# ble_blind_mover.net
KiCad netlist of a schematic drawn in EAGLE
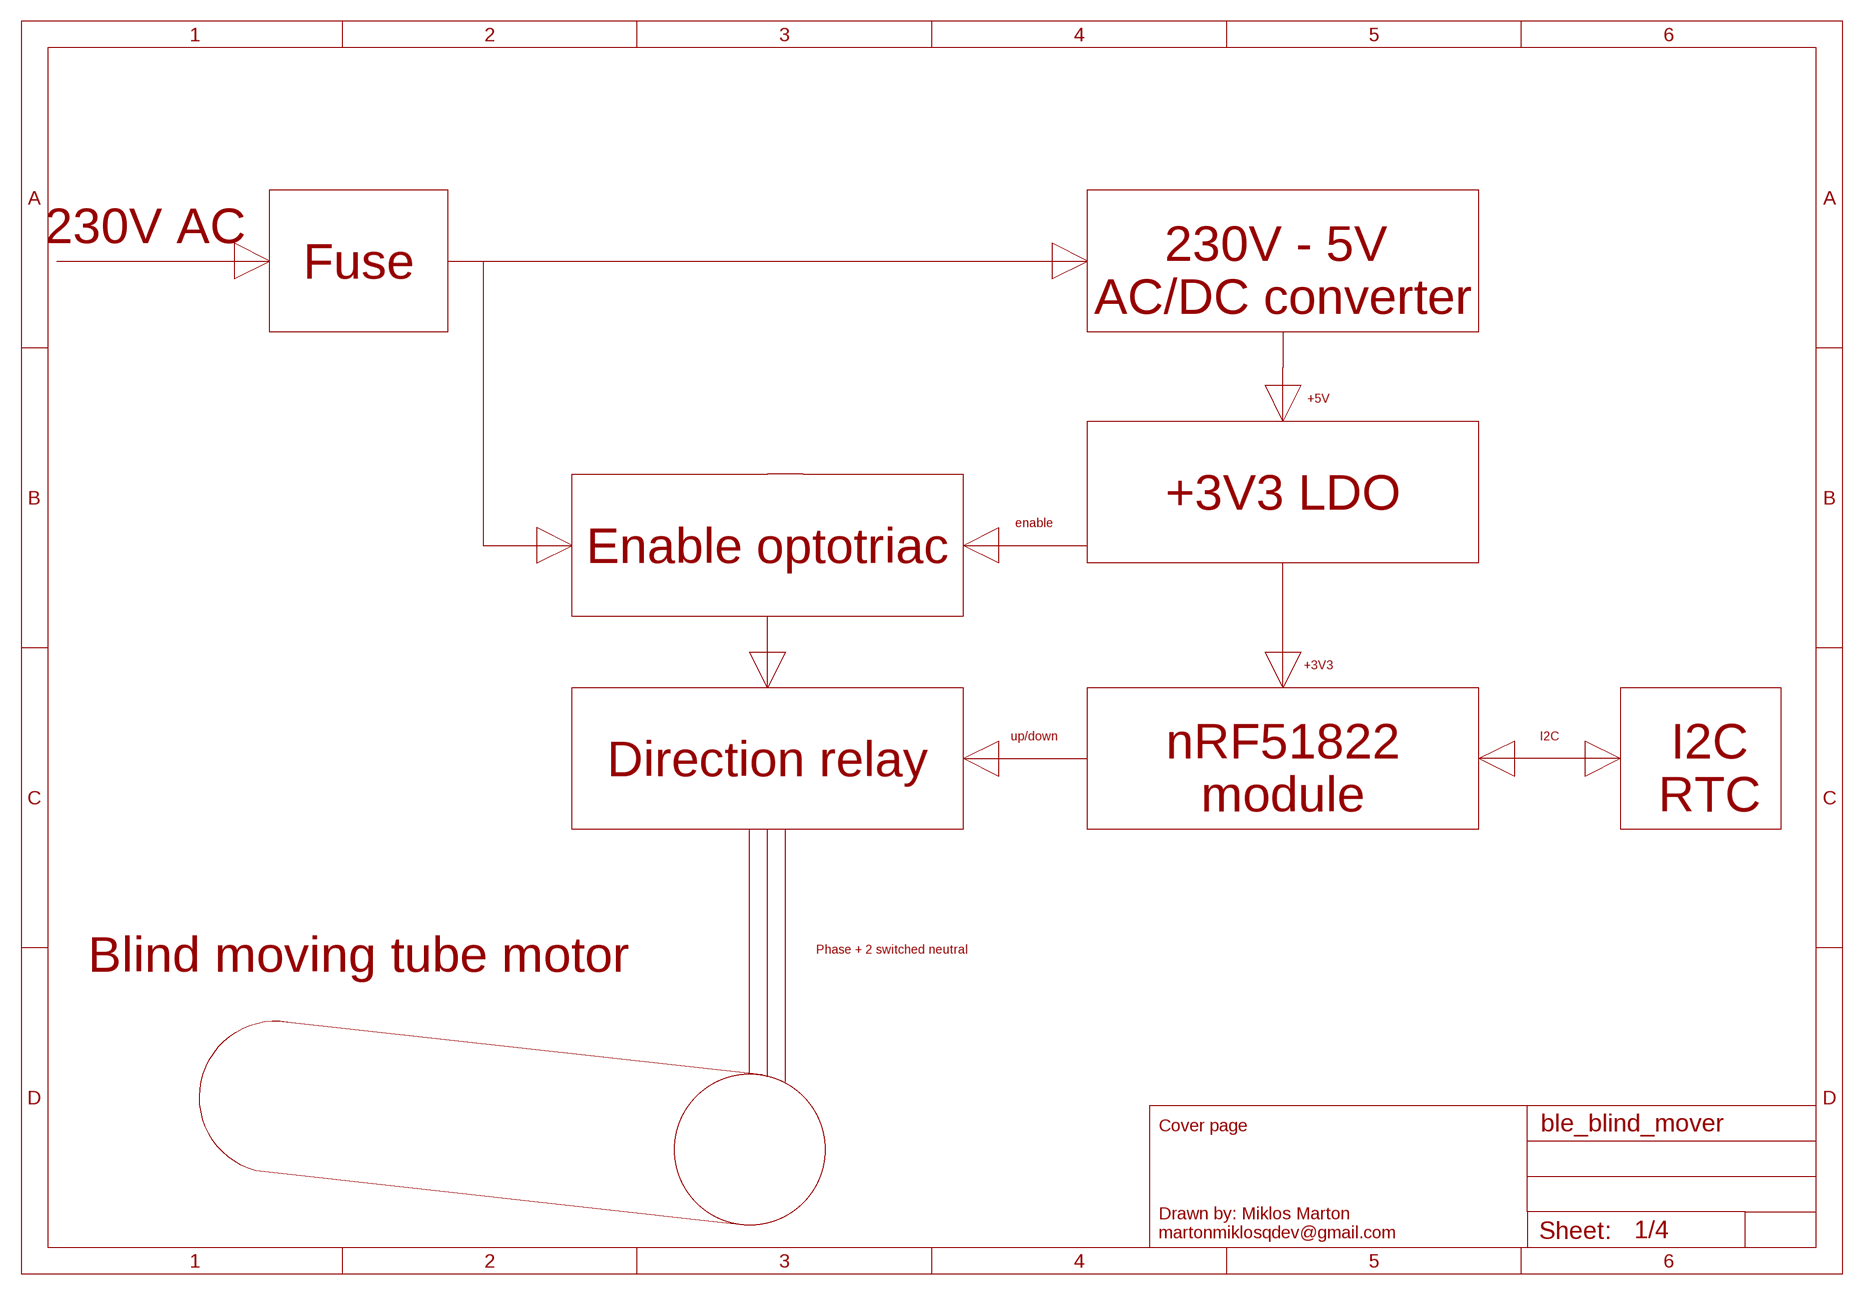
[diagram p0: schematic, sheet 1]
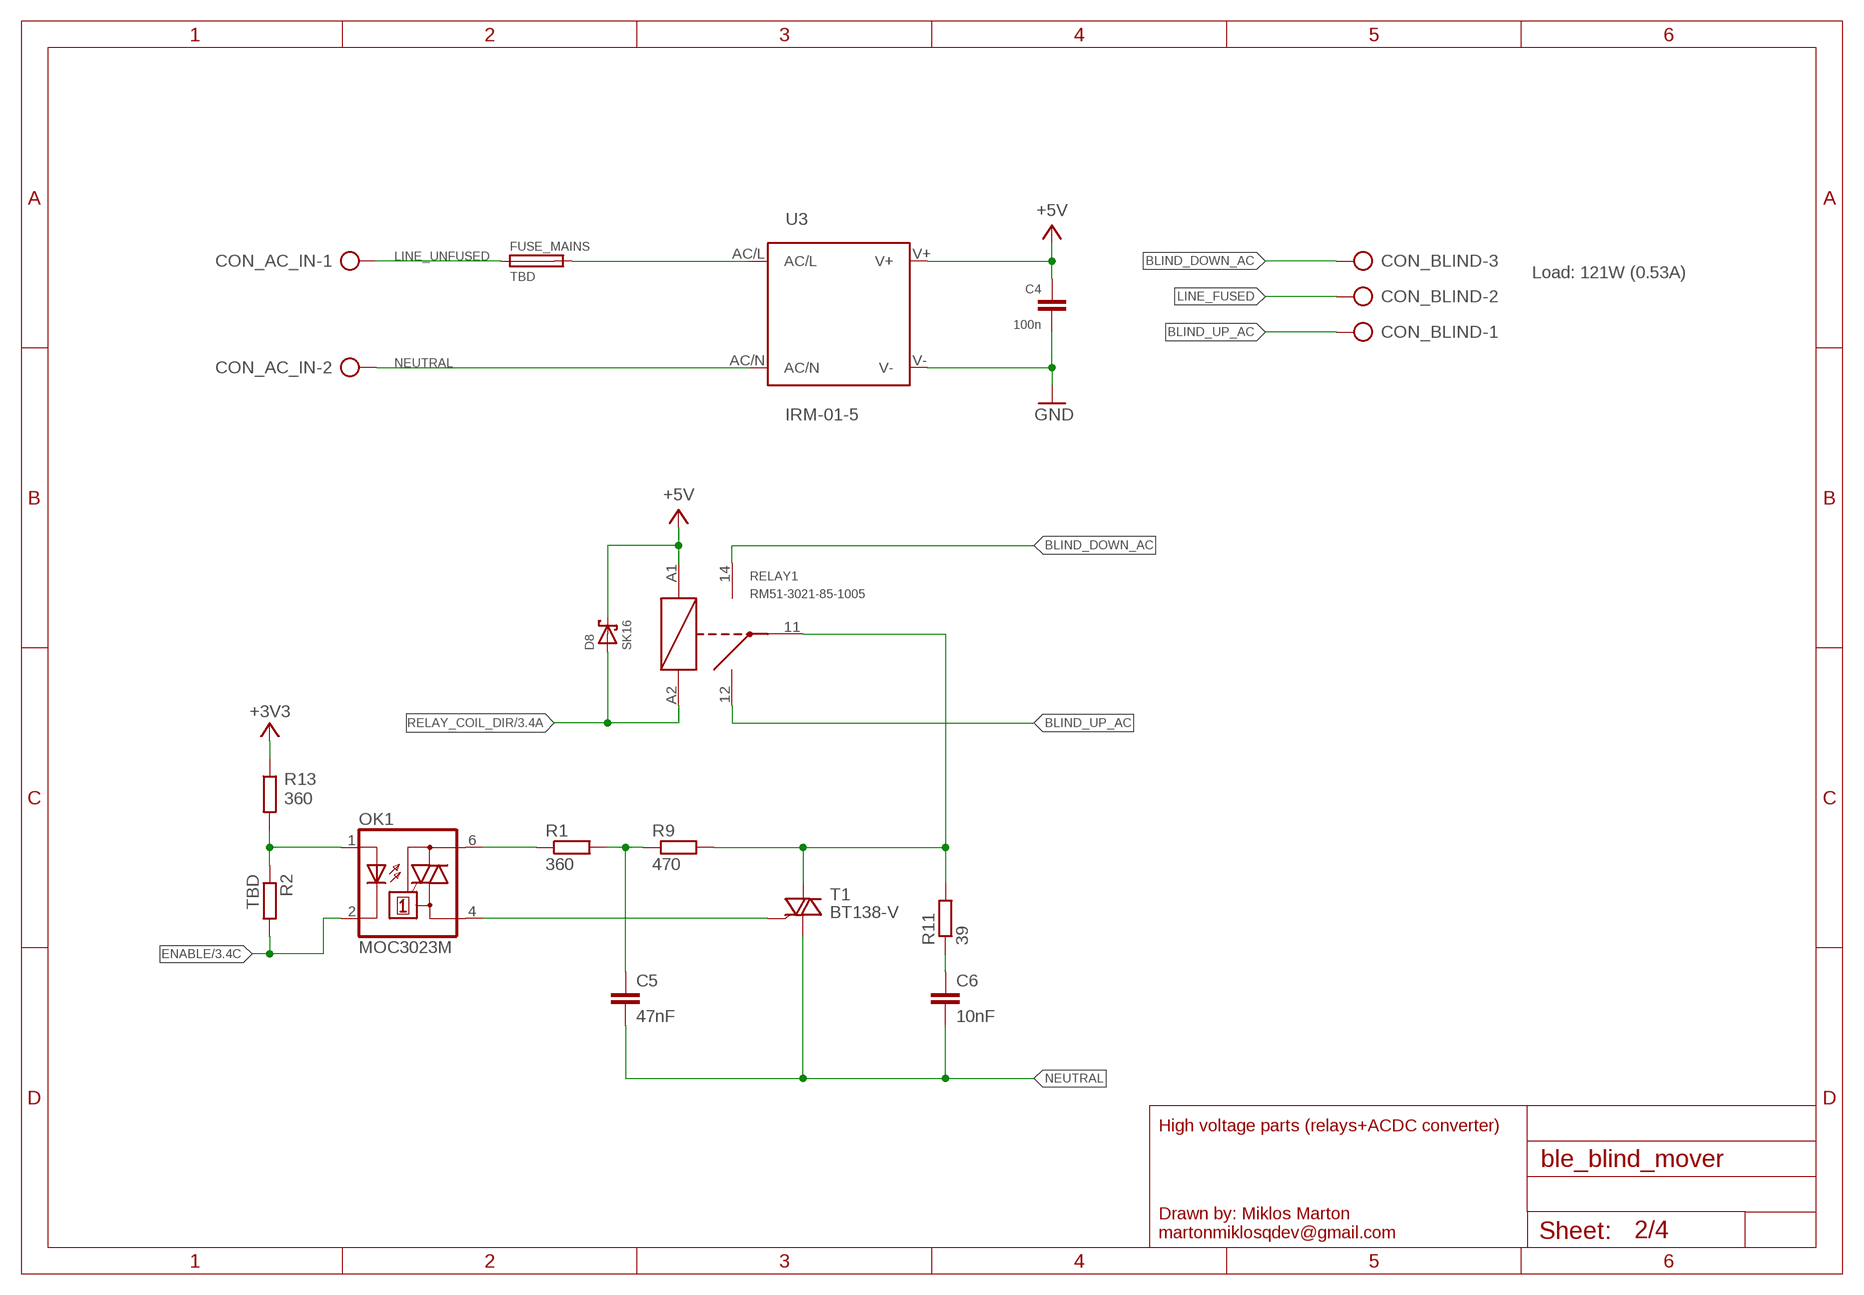
[diagram p1: schematic, sheet 2]
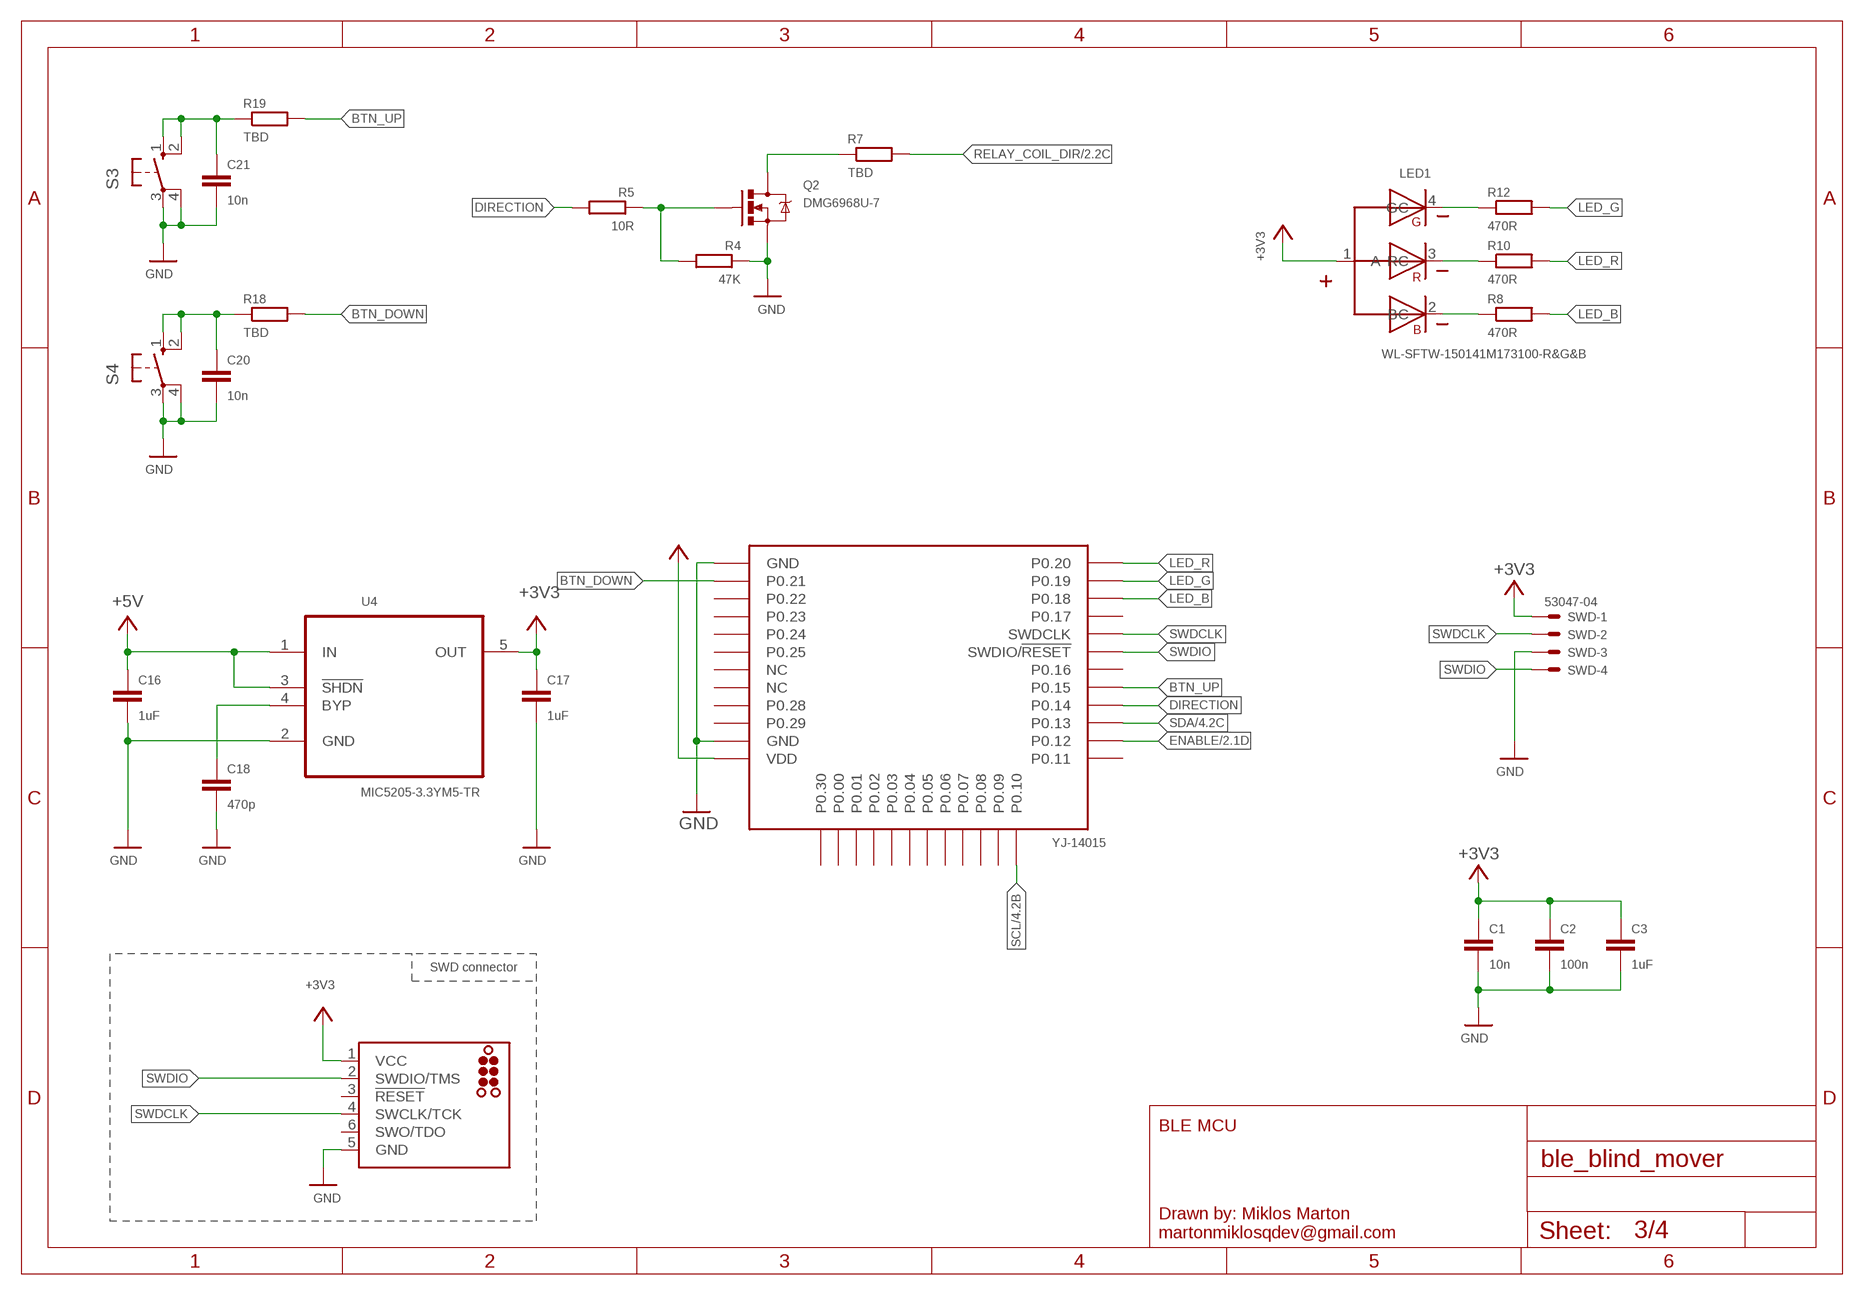
[diagram p2: schematic, sheet 3]
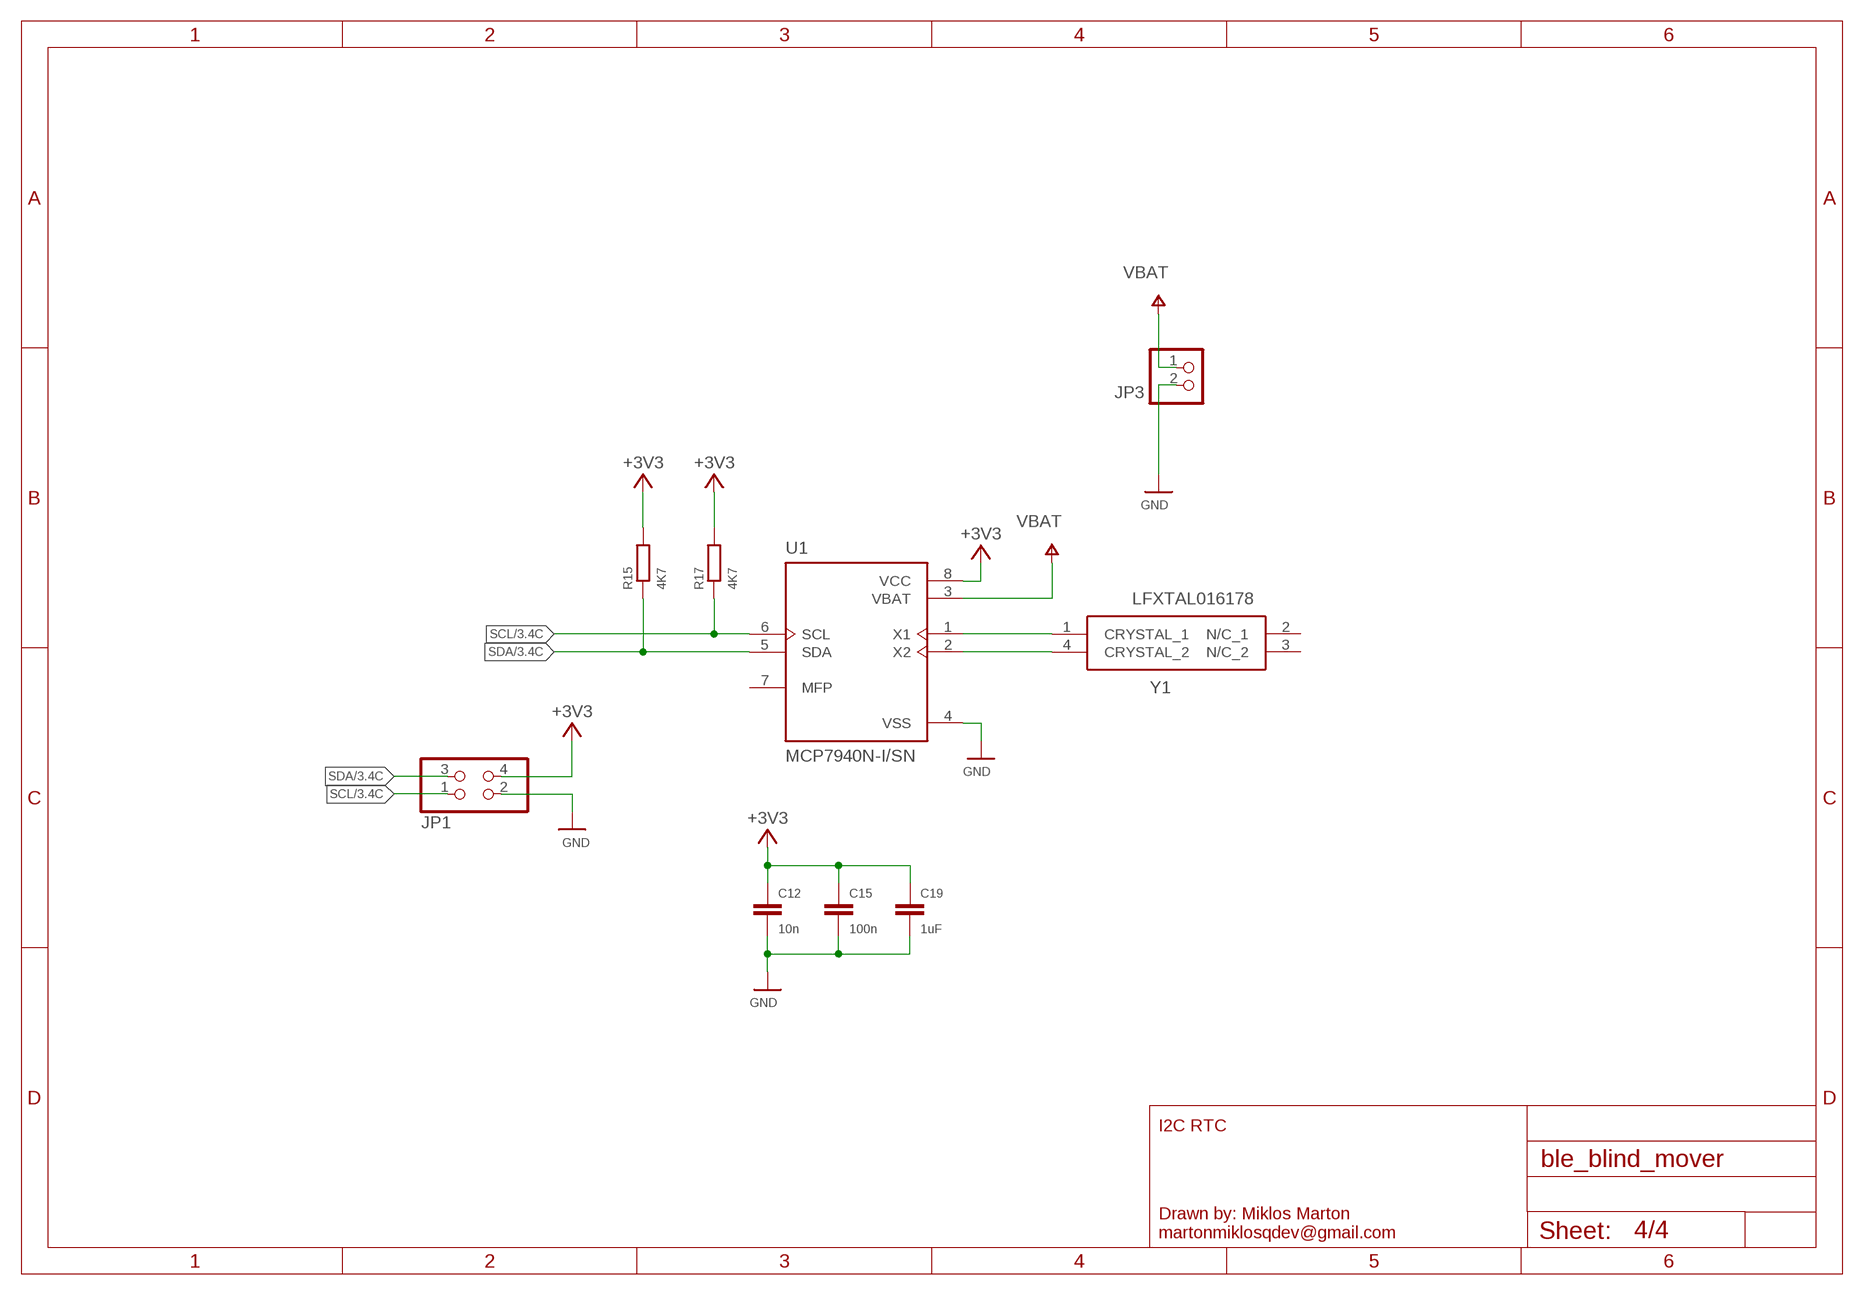
[diagram p3: schematic, sheet 4]

(export (version "E")
  (design (tool "Eeschema 10.0.6"))
  (components
    (comp (ref "C4")
      (value "100n")
      (footprint "eagle-import:C0603")
      (libsource (lib "eagle-import") (part "C-EUC0603"))
    )
    (comp (ref "C5")
      (value "47nF")
      (footprint "eagle-import:C025-030X050")
      (libsource (lib "eagle-import") (part "C-EU025-030X050"))
    )
    (comp (ref "C6")
      (value "10nF")
      (footprint "eagle-import:C025-030X050")
      (libsource (lib "eagle-import") (part "C-EU025-030X050"))
    )
    (comp (ref "CON_AC_IN")
      (value "AK500/2")
      (footprint "eagle-import:AK500_2")
      (libsource (lib "eagle-import") (part "AK500/2"))
    )
    (comp (ref "CON_BLIND")
      (value "AK500/3")
      (footprint "eagle-import:AK500_3")
      (libsource (lib "eagle-import") (part "AK500/3"))
    )
    (comp (ref "D8")
      (value "SK16")
      (footprint "eagle-import:DO-214AC")
      (libsource (lib "eagle-import") (part "SCHOTTKY-DIODESK12"))
    )
    (comp (ref "FUSE_MAINS")
      (value "TBD")
      (footprint "eagle-import:SH22,5")
      (fields (field (name "MF") "SCHURTER") (field (name "MPN") "0031.8201"))
      (libsource (lib "eagle-import") (part "SH22,5"))
    )
    (comp (ref "OK1")
      (value "MOC3023M")
      (footprint "eagle-import:DIL06")
      (fields (field (name "MF") "FAIRCHILD SEMICONDUCTOR") (field (name "MPN") "MOC3023-M"))
      (libsource (lib "eagle-import") (part "MOC30M23"))
    )
    (comp (ref "R1")
      (value "360")
      (footprint "eagle-import:R0805")
      (libsource (lib "eagle-import") (part "R-EU_R0805"))
    )
    (comp (ref "R2")
      (value "TBD")
      (footprint "eagle-import:R0603")
      (libsource (lib "eagle-import") (part "R-EU_R0603"))
    )
    (comp (ref "R9")
      (value "470")
      (footprint "eagle-import:R0805")
      (libsource (lib "eagle-import") (part "R-EU_R0805"))
    )
    (comp (ref "R11")
      (value "39")
      (footprint "eagle-import:0204V")
      (libsource (lib "eagle-import") (part "R-EU_0204/2V"))
    )
    (comp (ref "R13")
      (value "360")
      (footprint "eagle-import:R0603")
      (libsource (lib "eagle-import") (part "R-EU_R0603"))
    )
    (comp (ref "RELAY1")
      (value "RM51-3021-85-1005")
      (footprint "eagle-import:RM50-3011-XX-XXXX")
      (libsource (lib "eagle-import") (part "RM50-3011-XX-XXXX"))
    )
    (comp (ref "T1")
      (value "BT138-V")
      (footprint "eagle-import:TO220BV")
      (libsource (lib "eagle-import") (part "BT138-V"))
    )
    (comp (ref "U3")
      (value "IRM-01-5")
      (footprint "eagle-import:IRM_01_02")
      (libsource (lib "eagle-import") (part "IRM_01/02IRM_01/02"))
    )
    (comp (ref "C1")
      (value "10n")
      (footprint "eagle-import:C0603")
      (libsource (lib "eagle-import") (part "C-EUC0603"))
    )
    (comp (ref "C2")
      (value "100n")
      (footprint "eagle-import:C0603")
      (libsource (lib "eagle-import") (part "C-EUC0603"))
    )
    (comp (ref "C3")
      (value "1uF")
      (footprint "eagle-import:C0603")
      (libsource (lib "eagle-import") (part "C-EUC0603"))
    )
    (comp (ref "C16")
      (value "1uF")
      (footprint "eagle-import:C0603")
      (libsource (lib "eagle-import") (part "C-EUC0603"))
    )
    (comp (ref "C17")
      (value "1uF")
      (footprint "eagle-import:C0603")
      (libsource (lib "eagle-import") (part "C-EUC0603"))
    )
    (comp (ref "C18")
      (value "470p")
      (footprint "eagle-import:C0603")
      (libsource (lib "eagle-import") (part "C-EUC0603"))
    )
    (comp (ref "C20")
      (value "10n")
      (footprint "eagle-import:C0603")
      (libsource (lib "eagle-import") (part "C-EUC0603"))
    )
    (comp (ref "C21")
      (value "10n")
      (footprint "eagle-import:C0603")
      (libsource (lib "eagle-import") (part "C-EUC0603"))
    )
    (comp (ref "J2")
      (value "TC2030_SWD-MCP-NL")
      (footprint "eagle-import:TC2030-MCP-NL")
      (libsource (lib "eagle-import") (part "TC2030_SWD-MCP-NL"))
    )
    (comp (ref "LED1")
      (value "WL-SFTW-150141M173100-R&G&B")
      (footprint "eagle-import:3528-COMMON-ANODE")
      (libsource (lib "eagle-import") (part "WL-SFTW-150141M173100-R&G&B"))
    )
    (comp (ref "Q2")
      (value "DMG6968U-7")
      (footprint "eagle-import:SOT23-3")
      (libsource (lib "eagle-import") (part "MOSFET-NCHANNELSMD"))
    )
    (comp (ref "R4")
      (value "47K")
      (footprint "eagle-import:R0603")
      (libsource (lib "eagle-import") (part "R-EU_R0603"))
    )
    (comp (ref "R5")
      (value "10R")
      (footprint "eagle-import:R0603")
      (libsource (lib "eagle-import") (part "R-EU_R0603"))
    )
    (comp (ref "R7")
      (value "TBD")
      (footprint "eagle-import:R0603")
      (libsource (lib "eagle-import") (part "R-EU_R0603"))
    )
    (comp (ref "R8")
      (value "470R")
      (footprint "eagle-import:R0603")
      (libsource (lib "eagle-import") (part "R-EU_R0603"))
    )
    (comp (ref "R10")
      (value "470R")
      (footprint "eagle-import:R0603")
      (libsource (lib "eagle-import") (part "R-EU_R0603"))
    )
    (comp (ref "R12")
      (value "470R")
      (footprint "eagle-import:R0603")
      (libsource (lib "eagle-import") (part "R-EU_R0603"))
    )
    (comp (ref "R18")
      (value "TBD")
      (footprint "eagle-import:R0603")
      (libsource (lib "eagle-import") (part "R-EU_R0603"))
    )
    (comp (ref "R19")
      (value "TBD")
      (footprint "eagle-import:R0603")
      (libsource (lib "eagle-import") (part "R-EU_R0603"))
    )
    (comp (ref "S3")
      (value "10-XX")
      (footprint "eagle-import:B3F-10XX")
      (fields (field (name "MPN") "B3F-1000"))
      (libsource (lib "eagle-import") (part "10-XX"))
    )
    (comp (ref "S4")
      (value "10-XX")
      (footprint "eagle-import:B3F-10XX")
      (fields (field (name "MPN") "B3F-1000"))
      (libsource (lib "eagle-import") (part "10-XX"))
    )
    (comp (ref "SWD")
      (value "53047-04")
      (footprint "eagle-import:53047-04")
      (fields (field (name "MF") "WALDOM/MOLEX") (field (name "MPN") "53047-0410"))
      (libsource (lib "eagle-import") (part "53?-04047"))
    )
    (comp (ref "U2")
      (value "YJ-14015")
      (footprint "eagle-import:YJ-14015")
      (libsource (lib "eagle-import") (part "YJ-14015"))
    )
    (comp (ref "U4")
      (value "MIC5205-3.3YM5-TR")
      (footprint "eagle-import:SOT95P280X145-5N")
      (fields (field (name "MPN") "LT1761ES5-3.3#TRMPBF"))
      (libsource (lib "eagle-import") (part "LT1761ES5-3.3TRMPBF"))
    )
    (comp (ref "C12")
      (value "10n")
      (footprint "eagle-import:C0603")
      (libsource (lib "eagle-import") (part "C-EUC0603"))
    )
    (comp (ref "C15")
      (value "100n")
      (footprint "eagle-import:C0603")
      (libsource (lib "eagle-import") (part "C-EUC0603"))
    )
    (comp (ref "C19")
      (value "1uF")
      (footprint "eagle-import:C0603")
      (libsource (lib "eagle-import") (part "C-EUC0603"))
    )
    (comp (ref "JP1")
      (value "PINHD-2X2")
      (footprint "eagle-import:2X02")
      (libsource (lib "eagle-import") (part "PINHD-2X2"))
    )
    (comp (ref "JP3")
      (value "PINHD-1X2")
      (footprint "eagle-import:1X02")
      (libsource (lib "eagle-import") (part "PINHD-1X2"))
    )
    (comp (ref "R15")
      (value "4K7")
      (footprint "eagle-import:R0603")
      (libsource (lib "eagle-import") (part "R-EU_R0603"))
    )
    (comp (ref "R17")
      (value "4K7")
      (footprint "eagle-import:R0603")
      (libsource (lib "eagle-import") (part "R-EU_R0603"))
    )
    (comp (ref "U1")
      (value "MCP7940N-I/SN")
      (footprint "eagle-import:SOIC127P600X175-8N")
      (fields (field (name "MF") "Microchip"))
      (libsource (lib "eagle-import") (part "MCP7940N-I/SN"))
    )
    (comp (ref "Y1")
      (value "LFXTAL016178")
      (footprint "eagle-import:LFXTAL016178_1")
      (fields (field (name "RS_PART_NUMBER") "1484350"))
      (libsource (lib "eagle-import") (part "LFXTAL016178"))
    )
  )
  (nets
    (net (code "1") (name "+3V3") (class "Default")
      (node (ref "C1") (pin "1") (pinfunction "1_1") (pintype "passive"))
      (node (ref "C12") (pin "1") (pinfunction "1_1") (pintype "passive"))
      (node (ref "C15") (pin "1") (pinfunction "1_1") (pintype "passive"))
      (node (ref "C17") (pin "1") (pinfunction "1_1") (pintype "passive"))
      (node (ref "C19") (pin "1") (pinfunction "1_1") (pintype "passive"))
      (node (ref "C2") (pin "1") (pinfunction "1_1") (pintype "passive"))
      (node (ref "C3") (pin "1") (pinfunction "1_1") (pintype "passive"))
      (node (ref "J2") (pin "1") (pinfunction "VCC_1") (pintype "passive"))
      (node (ref "JP1") (pin "4") (pinfunction "4_4") (pintype "passive"))
      (node (ref "LED1") (pin "1") (pinfunction "A_1") (pintype "bidirectional"))
      (node (ref "R13") (pin "1") (pinfunction "1_1") (pintype "passive"))
      (node (ref "R15") (pin "2") (pinfunction "2_2") (pintype "passive"))
      (node (ref "R17") (pin "2") (pinfunction "2_2") (pintype "passive"))
      (node (ref "SWD") (pin "1") (pinfunction "S_1") (pintype "passive"))
      (node (ref "U1") (pin "8") (pinfunction "VCC_8") (pintype "power_in"))
      (node (ref "U2") (pin "VDD") (pinfunction "VDD_VDD") (pintype "passive"))
      (node (ref "U4") (pin "5") (pinfunction "OUT_5") (pintype "passive"))
    )
    (net (code "2") (name "+5V") (class "Default")
      (node (ref "C16") (pin "1") (pinfunction "1_1") (pintype "passive"))
      (node (ref "C4") (pin "1") (pinfunction "1_1") (pintype "passive"))
      (node (ref "D8") (pin "C") (pinfunction "C_C") (pintype "passive"))
      (node (ref "RELAY1") (pin "A1") (pinfunction "A1_A1") (pintype "bidirectional"))
      (node (ref "U3") (pin "V+") (pinfunction "V+_V+") (pintype "passive"))
      (node (ref "U4") (pin "1") (pinfunction "IN_1") (pintype "passive"))
      (node (ref "U4") (pin "3") (pinfunction "~{SHDN}_3") (pintype "input"))
    )
    (net (code "3") (name "BLIND_DOWN_AC") (class "Default")
      (node (ref "CON_BLIND") (pin "3") (pinfunction "KL_3") (pintype "passive"))
      (node (ref "RELAY1") (pin "14") (pinfunction "14_14") (pintype "bidirectional"))
    )
    (net (code "4") (name "BLIND_UP_AC") (class "Default")
      (node (ref "CON_BLIND") (pin "1") (pinfunction "KL_1") (pintype "passive"))
      (node (ref "RELAY1") (pin "12") (pinfunction "12_12") (pintype "bidirectional"))
    )
    (net (code "5") (name "BTN_DOWN") (class "Default")
      (node (ref "R18") (pin "2") (pinfunction "2_2") (pintype "passive"))
      (node (ref "U2") (pin "P.21") (pinfunction "P0.21_P.21") (pintype "bidirectional"))
    )
    (net (code "6") (name "BTN_UP") (class "Default")
      (node (ref "R19") (pin "2") (pinfunction "2_2") (pintype "passive"))
      (node (ref "U2") (pin "P.15") (pinfunction "P0.15_P.15") (pintype "bidirectional"))
    )
    (net (code "7") (name "DIRECTION") (class "Default")
      (node (ref "R5") (pin "2") (pinfunction "2_2") (pintype "passive"))
      (node (ref "U2") (pin "P.14") (pinfunction "P0.14_P.14") (pintype "bidirectional"))
    )
    (net (code "8") (name "ENABLE") (class "Default")
      (node (ref "OK1") (pin "2") (pinfunction "C_2") (pintype "passive"))
      (node (ref "R2") (pin "2") (pinfunction "2_2") (pintype "passive"))
      (node (ref "U2") (pin "P.12") (pinfunction "P0.12_P.12") (pintype "bidirectional"))
    )
    (net (code "9") (name "GND") (class "Default")
      (node (ref "C1") (pin "2") (pinfunction "2_2") (pintype "passive"))
      (node (ref "C12") (pin "2") (pinfunction "2_2") (pintype "passive"))
      (node (ref "C15") (pin "2") (pinfunction "2_2") (pintype "passive"))
      (node (ref "C16") (pin "2") (pinfunction "2_2") (pintype "passive"))
      (node (ref "C17") (pin "2") (pinfunction "2_2") (pintype "passive"))
      (node (ref "C18") (pin "2") (pinfunction "2_2") (pintype "passive"))
      (node (ref "C19") (pin "2") (pinfunction "2_2") (pintype "passive"))
      (node (ref "C2") (pin "2") (pinfunction "2_2") (pintype "passive"))
      (node (ref "C20") (pin "2") (pinfunction "2_2") (pintype "passive"))
      (node (ref "C21") (pin "2") (pinfunction "2_2") (pintype "passive"))
      (node (ref "C3") (pin "2") (pinfunction "2_2") (pintype "passive"))
      (node (ref "C4") (pin "2") (pinfunction "2_2") (pintype "passive"))
      (node (ref "J2") (pin "5") (pinfunction "GND_5") (pintype "passive"))
      (node (ref "JP1") (pin "2") (pinfunction "2_2") (pintype "passive"))
      (node (ref "JP3") (pin "2") (pinfunction "2_2") (pintype "passive"))
      (node (ref "Q2") (pin "2") (pinfunction "S_2") (pintype "passive"))
      (node (ref "R4") (pin "1") (pinfunction "1_1") (pintype "passive"))
      (node (ref "S3") (pin "3") (pinfunction "P_3") (pintype "passive"))
      (node (ref "S3") (pin "4") (pinfunction "P1_4") (pintype "passive"))
      (node (ref "S4") (pin "3") (pinfunction "P_3") (pintype "passive"))
      (node (ref "S4") (pin "4") (pinfunction "P1_4") (pintype "passive"))
      (node (ref "SWD") (pin "3") (pinfunction "S_3") (pintype "passive"))
      (node (ref "U1") (pin "4") (pinfunction "VSS_4") (pintype "power_in"))
      (node (ref "U2") (pin "GND") (pinfunction "GND_GND") (pintype "passive"))
      (node (ref "U2") (pin "GND@2") (pinfunction "GND_GND@2") (pintype "passive"))
      (node (ref "U3") (pin "V-") (pinfunction "V-_V-") (pintype "passive"))
      (node (ref "U4") (pin "2") (pinfunction "GND_2") (pintype "passive"))
    )
    (net (code "10") (name "LED_B") (class "Default")
      (node (ref "R8") (pin "2") (pinfunction "2_2") (pintype "passive"))
      (node (ref "U2") (pin "P.18") (pinfunction "P0.18_P.18") (pintype "bidirectional"))
    )
    (net (code "11") (name "LED_G") (class "Default")
      (node (ref "R12") (pin "2") (pinfunction "2_2") (pintype "passive"))
      (node (ref "U2") (pin "P.19") (pinfunction "P0.19_P.19") (pintype "bidirectional"))
    )
    (net (code "12") (name "LED_R") (class "Default")
      (node (ref "R10") (pin "2") (pinfunction "2_2") (pintype "passive"))
      (node (ref "U2") (pin "P.20") (pinfunction "P0.20_P.20") (pintype "bidirectional"))
    )
    (net (code "13") (name "LINE_FUSED") (class "Default")
      (node (ref "CON_BLIND") (pin "2") (pinfunction "KL_2") (pintype "passive"))
      (node (ref "FUSE_MAINS") (pin "2") (pinfunction "2_2") (pintype "passive"))
      (node (ref "U3") (pin "AC/L") (pinfunction "AC/L_AC/L") (pintype "input"))
    )
    (net (code "14") (name "LINE_UNFUSED") (class "Default")
      (node (ref "CON_AC_IN") (pin "1") (pinfunction "KL_1") (pintype "passive"))
      (node (ref "FUSE_MAINS") (pin "1") (pinfunction "1_1") (pintype "passive"))
    )
    (net (code "15") (name "NEUTRAL") (class "Default")
      (node (ref "C5") (pin "2") (pinfunction "2_2") (pintype "passive"))
      (node (ref "C6") (pin "2") (pinfunction "2_2") (pintype "passive"))
      (node (ref "CON_AC_IN") (pin "2") (pinfunction "KL_2") (pintype "passive"))
      (node (ref "T1") (pin "T1") (pinfunction "A1_T1") (pintype "passive"))
      (node (ref "U3") (pin "AC/N") (pinfunction "AC/N_AC/N") (pintype "input"))
    )
    (net (code "16") (name "Net-(C5-Pad1)") (class "Default")
      (node (ref "C5") (pin "1") (pinfunction "1_1") (pintype "passive"))
      (node (ref "R1") (pin "2") (pinfunction "2_2") (pintype "passive"))
      (node (ref "R9") (pin "1") (pinfunction "1_1") (pintype "passive"))
    )
    (net (code "17") (name "Net-(C6-Pad1)") (class "Default")
      (node (ref "C6") (pin "1") (pinfunction "1_1") (pintype "passive"))
      (node (ref "R11") (pin "1") (pinfunction "1_1") (pintype "passive"))
    )
    (net (code "18") (name "Net-(LED1-BC)") (class "Default")
      (node (ref "LED1") (pin "2") (pinfunction "BC_2") (pintype "bidirectional"))
      (node (ref "R8") (pin "1") (pinfunction "1_1") (pintype "passive"))
    )
    (net (code "19") (name "Net-(LED1-GC)") (class "Default")
      (node (ref "LED1") (pin "4") (pinfunction "GC_4") (pintype "bidirectional"))
      (node (ref "R12") (pin "1") (pinfunction "1_1") (pintype "passive"))
    )
    (net (code "20") (name "Net-(LED1-RC)") (class "Default")
      (node (ref "LED1") (pin "3") (pinfunction "RC_3") (pintype "bidirectional"))
      (node (ref "R10") (pin "1") (pinfunction "1_1") (pintype "passive"))
    )
    (net (code "21") (name "Net-(OK1-A)") (class "Default")
      (node (ref "OK1") (pin "1") (pinfunction "A_1") (pintype "passive"))
      (node (ref "R13") (pin "2") (pinfunction "2_2") (pintype "passive"))
      (node (ref "R2") (pin "1") (pinfunction "1_1") (pintype "passive"))
    )
    (net (code "22") (name "Net-(OK1-A1)") (class "Default")
      (node (ref "OK1") (pin "4") (pinfunction "A1_4") (pintype "passive"))
      (node (ref "T1") (pin "G") (pinfunction "G_G") (pintype "passive"))
    )
    (net (code "23") (name "Net-(OK1-A2)") (class "Default")
      (node (ref "OK1") (pin "6") (pinfunction "A2_6") (pintype "passive"))
      (node (ref "R1") (pin "1") (pinfunction "1_1") (pintype "passive"))
    )
    (net (code "24") (name "Net-(Q2-D)") (class "Default")
      (node (ref "Q2") (pin "3") (pinfunction "D_3") (pintype "passive"))
      (node (ref "R7") (pin "1") (pinfunction "1_1") (pintype "passive"))
    )
    (net (code "25") (name "Net-(Q2-G)") (class "Default")
      (node (ref "Q2") (pin "1") (pinfunction "G_1") (pintype "passive"))
      (node (ref "R4") (pin "2") (pinfunction "2_2") (pintype "passive"))
      (node (ref "R5") (pin "1") (pinfunction "1_1") (pintype "passive"))
    )
    (net (code "26") (name "Net-(S3-S)") (class "Default")
      (node (ref "C21") (pin "1") (pinfunction "1_1") (pintype "passive"))
      (node (ref "R19") (pin "1") (pinfunction "1_1") (pintype "passive"))
      (node (ref "S3") (pin "1") (pinfunction "S_1") (pintype "passive"))
      (node (ref "S3") (pin "2") (pinfunction "S1_2") (pintype "passive"))
    )
    (net (code "27") (name "Net-(S4-S)") (class "Default")
      (node (ref "C20") (pin "1") (pinfunction "1_1") (pintype "passive"))
      (node (ref "R18") (pin "1") (pinfunction "1_1") (pintype "passive"))
      (node (ref "S4") (pin "1") (pinfunction "S_1") (pintype "passive"))
      (node (ref "S4") (pin "2") (pinfunction "S1_2") (pintype "passive"))
    )
    (net (code "28") (name "Net-(T1-A2)") (class "Default")
      (node (ref "R11") (pin "2") (pinfunction "2_2") (pintype "passive"))
      (node (ref "R9") (pin "2") (pinfunction "2_2") (pintype "passive"))
      (node (ref "RELAY1") (pin "11") (pinfunction "11_11") (pintype "bidirectional"))
      (node (ref "T1") (pin "T2") (pinfunction "A2_T2") (pintype "passive"))
    )
    (net (code "29") (name "Net-(U1-X1)") (class "Default")
      (node (ref "U1") (pin "1") (pinfunction "X1_1") (pintype "input"))
      (node (ref "Y1") (pin "1") (pinfunction "CRYSTAL_1_1") (pintype "bidirectional"))
    )
    (net (code "30") (name "Net-(U1-X2)") (class "Default")
      (node (ref "U1") (pin "2") (pinfunction "X2_2") (pintype "output"))
      (node (ref "Y1") (pin "4") (pinfunction "CRYSTAL_2_4") (pintype "bidirectional"))
    )
    (net (code "31") (name "Net-(U4-BYP)") (class "Default")
      (node (ref "C18") (pin "1") (pinfunction "1_1") (pintype "passive"))
      (node (ref "U4") (pin "4") (pinfunction "BYP_4") (pintype "passive"))
    )
    (net (code "32") (name "RELAY_COIL_DIR") (class "Default")
      (node (ref "D8") (pin "A") (pinfunction "A_A") (pintype "passive"))
      (node (ref "R7") (pin "2") (pinfunction "2_2") (pintype "passive"))
      (node (ref "RELAY1") (pin "A2") (pinfunction "A2_A2") (pintype "bidirectional"))
    )
    (net (code "33") (name "SCL") (class "Default")
      (node (ref "JP1") (pin "1") (pinfunction "1_1") (pintype "passive"))
      (node (ref "R17") (pin "1") (pinfunction "1_1") (pintype "passive"))
      (node (ref "U1") (pin "6") (pinfunction "SCL_6") (pintype "input"))
      (node (ref "U2") (pin "P.10") (pinfunction "P0.10_P.10") (pintype "bidirectional"))
    )
    (net (code "34") (name "SDA") (class "Default")
      (node (ref "JP1") (pin "3") (pinfunction "3_3") (pintype "passive"))
      (node (ref "R15") (pin "1") (pinfunction "1_1") (pintype "passive"))
      (node (ref "U1") (pin "5") (pinfunction "SDA_5") (pintype "bidirectional"))
      (node (ref "U2") (pin "P.13") (pinfunction "P0.13_P.13") (pintype "bidirectional"))
    )
    (net (code "35") (name "SWDCLK") (class "Default")
      (node (ref "J2") (pin "4") (pinfunction "SWCLK/TCK_4") (pintype "output"))
      (node (ref "SWD") (pin "2") (pinfunction "S_2") (pintype "passive"))
      (node (ref "U2") (pin "SWDCLK") (pinfunction "SWDCLK_SWDCLK") (pintype "input"))
    )
    (net (code "36") (name "SWDIO") (class "Default")
      (node (ref "J2") (pin "2") (pinfunction "SWDIO/TMS_2") (pintype "bidirectional"))
      (node (ref "SWD") (pin "4") (pinfunction "S_4") (pintype "passive"))
      (node (ref "U2") (pin "SWDIO") (pinfunction "SWDIO/~{RESET}_SWDIO") (pintype "bidirectional"))
    )
    (net (code "37") (name "VBAT") (class "Default")
      (node (ref "JP3") (pin "1") (pinfunction "1_1") (pintype "passive"))
      (node (ref "U1") (pin "3") (pinfunction "VBAT_3") (pintype "power_in"))
    )
    (net (code "38") (name "unconnected-(J2-SWO{slash}TDO-Pad6)") (class "Default")
      (node (ref "J2") (pin "6") (pinfunction "SWO/TDO_6") (pintype "bidirectional"))
    )
    (net (code "39") (name "unconnected-(J2-~{RESET}-Pad3)") (class "Default")
      (node (ref "J2") (pin "3") (pinfunction "~{RESET}_3") (pintype "output"))
    )
    (net (code "40") (name "unconnected-(U1-MFP-Pad7)") (class "Default")
      (node (ref "U1") (pin "7") (pinfunction "MFP_7") (pintype "bidirectional"))
    )
    (net (code "41") (name "unconnected-(U2-NC-PadP.26)") (class "Default")
      (node (ref "U2") (pin "P.26") (pinfunction "NC_P.26") (pintype "no_connect"))
    )
    (net (code "42") (name "unconnected-(U2-NC-PadP.27)") (class "Default")
      (node (ref "U2") (pin "P.27") (pinfunction "NC_P.27") (pintype "no_connect"))
    )
    (net (code "43") (name "unconnected-(U2-P0.00-PadP.00)") (class "Default")
      (node (ref "U2") (pin "P.00") (pinfunction "P0.00_P.00") (pintype "bidirectional"))
    )
    (net (code "44") (name "unconnected-(U2-P0.01-PadP.01)") (class "Default")
      (node (ref "U2") (pin "P.01") (pinfunction "P0.01_P.01") (pintype "bidirectional"))
    )
    (net (code "45") (name "unconnected-(U2-P0.02-PadP.02)") (class "Default")
      (node (ref "U2") (pin "P.02") (pinfunction "P0.02_P.02") (pintype "bidirectional"))
    )
    (net (code "46") (name "unconnected-(U2-P0.03-PadP.03)") (class "Default")
      (node (ref "U2") (pin "P.03") (pinfunction "P0.03_P.03") (pintype "bidirectional"))
    )
    (net (code "47") (name "unconnected-(U2-P0.04-PadP.04)") (class "Default")
      (node (ref "U2") (pin "P.04") (pinfunction "P0.04_P.04") (pintype "bidirectional"))
    )
    (net (code "48") (name "unconnected-(U2-P0.05-PadP.05)") (class "Default")
      (node (ref "U2") (pin "P.05") (pinfunction "P0.05_P.05") (pintype "bidirectional"))
    )
    (net (code "49") (name "unconnected-(U2-P0.06-PadP.06)") (class "Default")
      (node (ref "U2") (pin "P.06") (pinfunction "P0.06_P.06") (pintype "bidirectional"))
    )
    (net (code "50") (name "unconnected-(U2-P0.07-PadP.07)") (class "Default")
      (node (ref "U2") (pin "P.07") (pinfunction "P0.07_P.07") (pintype "bidirectional"))
    )
    (net (code "51") (name "unconnected-(U2-P0.08-PadP.08)") (class "Default")
      (node (ref "U2") (pin "P.08") (pinfunction "P0.08_P.08") (pintype "bidirectional"))
    )
    (net (code "52") (name "unconnected-(U2-P0.09-PadP.09)") (class "Default")
      (node (ref "U2") (pin "P.09") (pinfunction "P0.09_P.09") (pintype "bidirectional"))
    )
    (net (code "53") (name "unconnected-(U2-P0.11-PadP.11)") (class "Default")
      (node (ref "U2") (pin "P.11") (pinfunction "P0.11_P.11") (pintype "bidirectional"))
    )
    (net (code "54") (name "unconnected-(U2-P0.16-PadP.16)") (class "Default")
      (node (ref "U2") (pin "P.16") (pinfunction "P0.16_P.16") (pintype "bidirectional"))
    )
    (net (code "55") (name "unconnected-(U2-P0.17-PadP.17)") (class "Default")
      (node (ref "U2") (pin "P.17") (pinfunction "P0.17_P.17") (pintype "bidirectional"))
    )
    (net (code "56") (name "unconnected-(U2-P0.22-PadP.22)") (class "Default")
      (node (ref "U2") (pin "P.22") (pinfunction "P0.22_P.22") (pintype "bidirectional"))
    )
    (net (code "57") (name "unconnected-(U2-P0.23-PadP.23)") (class "Default")
      (node (ref "U2") (pin "P.23") (pinfunction "P0.23_P.23") (pintype "bidirectional"))
    )
    (net (code "58") (name "unconnected-(U2-P0.24-PadP.24)") (class "Default")
      (node (ref "U2") (pin "P.24") (pinfunction "P0.24_P.24") (pintype "bidirectional"))
    )
    (net (code "59") (name "unconnected-(U2-P0.25-PadP.25)") (class "Default")
      (node (ref "U2") (pin "P.25") (pinfunction "P0.25_P.25") (pintype "bidirectional"))
    )
    (net (code "60") (name "unconnected-(U2-P0.28-PadP.28)") (class "Default")
      (node (ref "U2") (pin "P.28") (pinfunction "P0.28_P.28") (pintype "bidirectional"))
    )
    (net (code "61") (name "unconnected-(U2-P0.29-PadP.29)") (class "Default")
      (node (ref "U2") (pin "P.29") (pinfunction "P0.29_P.29") (pintype "bidirectional"))
    )
    (net (code "62") (name "unconnected-(U2-P0.30-PadP.30)") (class "Default")
      (node (ref "U2") (pin "P.30") (pinfunction "P0.30_P.30") (pintype "bidirectional"))
    )
    (net (code "63") (name "unconnected-(Y1-N{slash}C_1-Pad2)") (class "Default")
      (node (ref "Y1") (pin "2") (pinfunction "N/C_1_2") (pintype "bidirectional"))
    )
    (net (code "64") (name "unconnected-(Y1-N{slash}C_2-Pad3)") (class "Default")
      (node (ref "Y1") (pin "3") (pinfunction "N/C_2_3") (pintype "bidirectional"))
    )
  )
)
